# PIC32ETH_Usb.net
KiCad netlist of a schematic drawn in Altium Designer
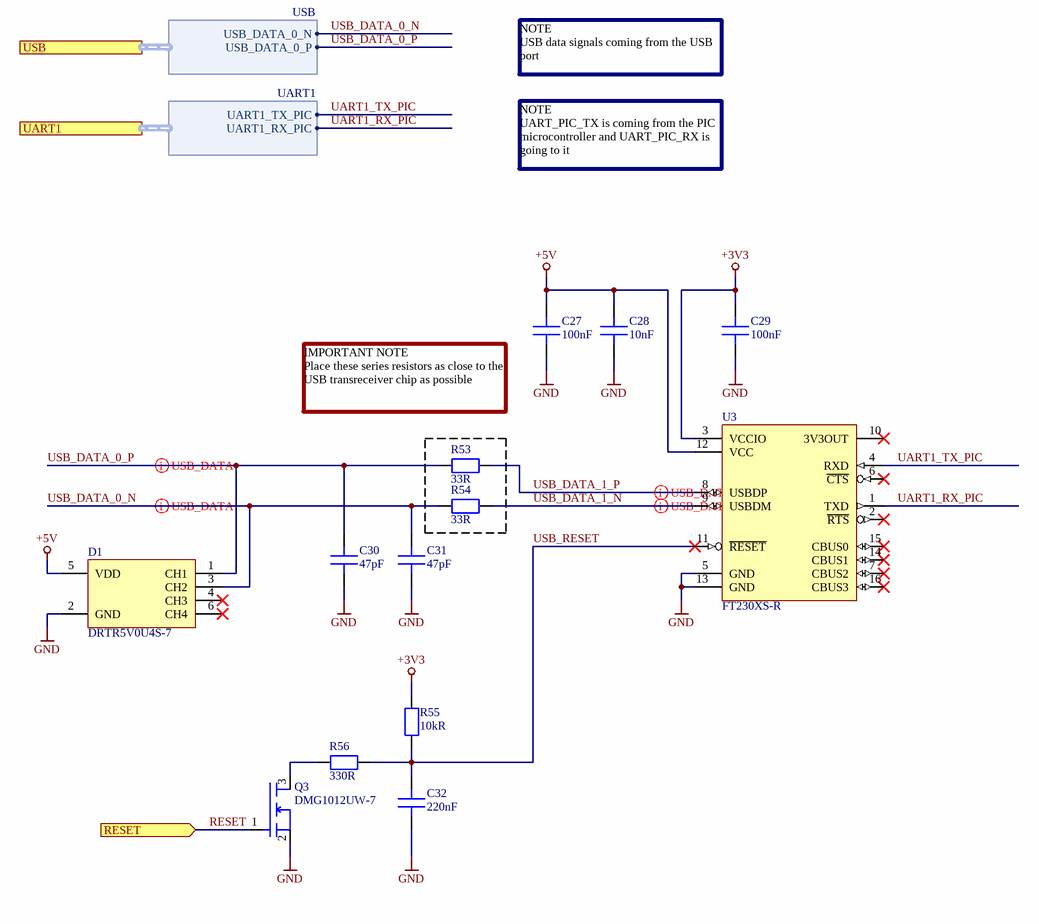
[diagram p0: PIC32ETH_Usb.SchDoc]

(export (version "E")
  (design (tool "Eeschema 10.0.6"))
  (components
    (comp (ref "C27")
      (value "100nF")
      (footprint "C_CHIP2012N")
      (description "C CERAMIC 100nF 50V 10% 2012")
      (fields (field (name "MANUFACTURER") "Kemet") (field (name "PART NUMBER") "C0805C104K5RACTU"))
      (libsource (lib "PIC32ETH") (part "C_C0805C104K5RACTU"))
    )
    (comp (ref "C28")
      (value "10nF")
      (footprint "C_CHIP2012N")
      (description "C CERAMIC 10nF 50V 10% 2012")
      (fields (field (name "MANUFACTURER") "Kemet") (field (name "PART NUMBER") "C0805C103K5RACTU"))
      (libsource (lib "PIC32ETH") (part "C_C0805C103K5RACTU"))
    )
    (comp (ref "C29")
      (value "100nF")
      (footprint "C_CHIP2012N")
      (description "C CERAMIC 100nF 50V 10% 2012")
      (fields (field (name "MANUFACTURER") "Kemet") (field (name "PART NUMBER") "C0805C104K5RACTU"))
      (libsource (lib "PIC32ETH") (part "C_C0805C104K5RACTU"))
    )
    (comp (ref "C30")
      (value "47pF")
      (footprint "C_CHIP2012N")
      (description "C CERAMIC 47pF 50V 10% 2012")
      (fields (field (name "MANUFACTURER") "Kemet") (field (name "PART NUMBER") "C0805C470K5GACTU"))
      (libsource (lib "PIC32ETH") (part "C_C0805C470K5GACTU"))
    )
    (comp (ref "C31")
      (value "47pF")
      (footprint "C_CHIP2012N")
      (description "C CERAMIC 47pF 50V 10% 2012")
      (fields (field (name "MANUFACTURER") "Kemet") (field (name "PART NUMBER") "C0805C470K5GACTU"))
      (libsource (lib "PIC32ETH") (part "C_C0805C470K5GACTU"))
    )
    (comp (ref "C32")
      (value "220nF")
      (footprint "C_CHIP2012N")
      (description "C CERAMIC 220nF 50V 10% 2012")
      (fields (field (name "MANUFACTURER") "Kemet") (field (name "PART NUMBER") "C0805C224K5RACTU"))
      (libsource (lib "PIC32ETH") (part "C_C0805C224K5RACTU"))
    )
    (comp (ref "D1")
      (value "DRTR5V0U4S-7")
      (footprint "D_SOT65P210X100-6N")
      (description "D TVS 5.5V 6V 200mW SOT-363")
      (fields (field (name "MANUFACTURER") "Diodes Incorporated") (field (name "POWER") "200mW"))
      (libsource (lib "PIC32ETH") (part "D_DRTR5V0U4S-7"))
    )
    (comp (ref "Q3")
      (value "DMG1012UW-7")
      (footprint "Q_SOT65P210X100-3N")
      (description "Q MOSFET N-CH 20V 1A SOT-323")
      (fields (field (name "MANUFACTURER") "Diodes Incorporated") (field (name "POWER") "290mW"))
      (libsource (lib "PIC32ETH") (part "Q_DMG1012UW-7"))
    )
    (comp (ref "R53")
      (value "33R")
      (footprint "R_CHIP2012N")
      (description "R SMT 33R 1% 125mW 2012")
      (fields
        (field (name "MANUFACTURER") "Stackpole Electronics Inc")
        (field (name "PART NUMBER") "RMCF0805FT33R0")
      )
      (libsource (lib "PIC32ETH") (part "R_RMCF0805FT33R0"))
    )
    (comp (ref "R54")
      (value "33R")
      (footprint "R_CHIP2012N")
      (description "R SMT 33R 1% 125mW 2012")
      (fields
        (field (name "MANUFACTURER") "Stackpole Electronics Inc")
        (field (name "PART NUMBER") "RMCF0805FT33R0")
      )
      (libsource (lib "PIC32ETH") (part "R_RMCF0805FT33R0"))
    )
    (comp (ref "R55")
      (value "10kR")
      (footprint "R_CHIP2012N")
      (description "R SMT 10kR 1% 125mW 2012")
      (fields
        (field (name "MANUFACTURER") "Stackpole Electronics Inc")
        (field (name "PART NUMBER") "RMCF0805FT10K0")
      )
      (libsource (lib "PIC32ETH") (part "R_RMCF0805FT10K0"))
    )
    (comp (ref "R56")
      (value "330R")
      (footprint "R_CHIP2012N")
      (description "R SMT 330R 1% 125mW 2012")
      (fields
        (field (name "MANUFACTURER") "Stackpole Electronics Inc")
        (field (name "PART NUMBER") "RMCF0805FT330R")
      )
      (libsource (lib "PIC32ETH") (part "R_RMCF0805FT330R"))
    )
    (comp (ref "U3")
      (value "FT230XS-R")
      (footprint "U_TSOP64P600X135-16N")
      (description "U TRANSCEIVER UART-USB 16-SSOP")
      (fields (field (name "MANUFACTURER") "FTDI"))
      (libsource (lib "PIC32ETH") (part "U_FT230XS-R"))
    )
  )
  (nets
    (net (code "3") (name "+3V3") (class "Default")
      (node (ref "C29") (pin "1") (pinfunction "1_1") (pintype "passive"))
      (node (ref "R55") (pin "2") (pinfunction "2_2") (pintype "passive"))
      (node (ref "U3") (pin "3") (pinfunction "VCCIO_3") (pintype "power_in"))
    )
    (net (code "4") (name "+5V") (class "Default")
      (node (ref "C27") (pin "1") (pinfunction "1_1") (pintype "passive"))
      (node (ref "C28") (pin "2") (pinfunction "2_2") (pintype "passive"))
      (node (ref "D1") (pin "5") (pinfunction "VDD_5") (pintype "power_in"))
      (node (ref "U3") (pin "12") (pinfunction "VCC_12") (pintype "power_in"))
    )
    (net (code "5") (name "/RESET") (class "Default")
      (node (ref "Q3") (pin "1") (pinfunction "G_1") (pintype "passive"))
    )
    (net (code "6") (name "/UART1_RX_PIC") (class "Default")
      (node (ref "U3") (pin "1") (pinfunction "TXD_1") (pintype "output"))
    )
    (net (code "7") (name "/UART1_TX_PIC") (class "Default")
      (node (ref "U3") (pin "4") (pinfunction "RXD_4") (pintype "input"))
    )
    (net (code "8") (name "/USB_DATA_0_N") (class "Default")
      (node (ref "C31") (pin "2") (pinfunction "2_2") (pintype "passive"))
      (node (ref "D1") (pin "3") (pinfunction "CH2_3") (pintype "passive"))
      (node (ref "R54") (pin "1") (pinfunction "1_1") (pintype "passive"))
    )
    (net (code "9") (name "/USB_DATA_0_P") (class "Default")
      (node (ref "C30") (pin "2") (pinfunction "2_2") (pintype "passive"))
      (node (ref "D1") (pin "1") (pinfunction "CH1_1") (pintype "passive"))
      (node (ref "R53") (pin "1") (pinfunction "1_1") (pintype "passive"))
    )
    (net (code "10") (name "/USB_DATA_1_N") (class "Default")
      (node (ref "R54") (pin "2") (pinfunction "2_2") (pintype "passive"))
      (node (ref "U3") (pin "9") (pinfunction "USBDM_9") (pintype "bidirectional"))
    )
    (net (code "11") (name "/USB_DATA_1_P") (class "Default")
      (node (ref "R53") (pin "2") (pinfunction "2_2") (pintype "passive"))
      (node (ref "U3") (pin "8") (pinfunction "USBDP_8") (pintype "bidirectional"))
    )
    (net (code "12") (name "/USB_RESET") (class "Default")
      (node (ref "C32") (pin "2") (pinfunction "2_2") (pintype "passive"))
      (node (ref "R55") (pin "1") (pinfunction "1_1") (pintype "passive"))
      (node (ref "R56") (pin "2") (pinfunction "2_2") (pintype "passive"))
      (node (ref "U3") (pin "11") (pinfunction "~{RESET}_11") (pintype "input"))
    )
    (net (code "15") (name "GND") (class "Default")
      (node (ref "C27") (pin "2") (pinfunction "2_2") (pintype "passive"))
      (node (ref "C28") (pin "1") (pinfunction "1_1") (pintype "passive"))
      (node (ref "C29") (pin "2") (pinfunction "2_2") (pintype "passive"))
      (node (ref "C30") (pin "1") (pinfunction "1_1") (pintype "passive"))
      (node (ref "C31") (pin "1") (pinfunction "1_1") (pintype "passive"))
      (node (ref "C32") (pin "1") (pinfunction "1_1") (pintype "passive"))
      (node (ref "D1") (pin "2") (pinfunction "GND_2") (pintype "power_in"))
      (node (ref "Q3") (pin "2") (pinfunction "S_2") (pintype "passive"))
      (node (ref "U3") (pin "13") (pinfunction "GND_13") (pintype "power_in"))
      (node (ref "U3") (pin "5") (pinfunction "GND_5") (pintype "power_in"))
    )
    (net (code "16") (name "Net-(Q3-D)") (class "Default")
      (node (ref "Q3") (pin "3") (pinfunction "D_3") (pintype "passive"))
      (node (ref "R56") (pin "1") (pinfunction "1_1") (pintype "passive"))
    )
    (net (code "17") (name "unconnected-(D1-CH3-Pad4)") (class "Default")
      (node (ref "D1") (pin "4") (pinfunction "CH3_4") (pintype "passive+no_connect"))
    )
    (net (code "18") (name "unconnected-(D1-CH4-Pad6)") (class "Default")
      (node (ref "D1") (pin "6") (pinfunction "CH4_6") (pintype "passive+no_connect"))
    )
    (net (code "19") (name "unconnected-(U3-3V3OUT-Pad10)") (class "Default")
      (node (ref "U3") (pin "10") (pinfunction "3V3OUT_10") (pintype "power_in+no_connect"))
    )
    (net (code "20") (name "unconnected-(U3-CBUS0-Pad15)") (class "Default")
      (node (ref "U3") (pin "15") (pinfunction "CBUS0_15") (pintype "bidirectional+no_connect"))
    )
    (net (code "21") (name "unconnected-(U3-CBUS1-Pad14)") (class "Default")
      (node (ref "U3") (pin "14") (pinfunction "CBUS1_14") (pintype "bidirectional+no_connect"))
    )
    (net (code "22") (name "unconnected-(U3-CBUS2-Pad7)") (class "Default")
      (node (ref "U3") (pin "7") (pinfunction "CBUS2_7") (pintype "bidirectional+no_connect"))
    )
    (net (code "23") (name "unconnected-(U3-CBUS3-Pad16)") (class "Default")
      (node (ref "U3") (pin "16") (pinfunction "CBUS3_16") (pintype "bidirectional+no_connect"))
    )
    (net (code "24") (name "unconnected-(U3-~{CTS}-Pad6)") (class "Default")
      (node (ref "U3") (pin "6") (pinfunction "~{CTS}_6") (pintype "input+no_connect"))
    )
    (net (code "25") (name "unconnected-(U3-~{RTS}-Pad2)") (class "Default")
      (node (ref "U3") (pin "2") (pinfunction "~{RTS}_2") (pintype "output+no_connect"))
    )
  )
)
